# stmdc.net
KiCad netlist of a schematic drawn in EAGLE
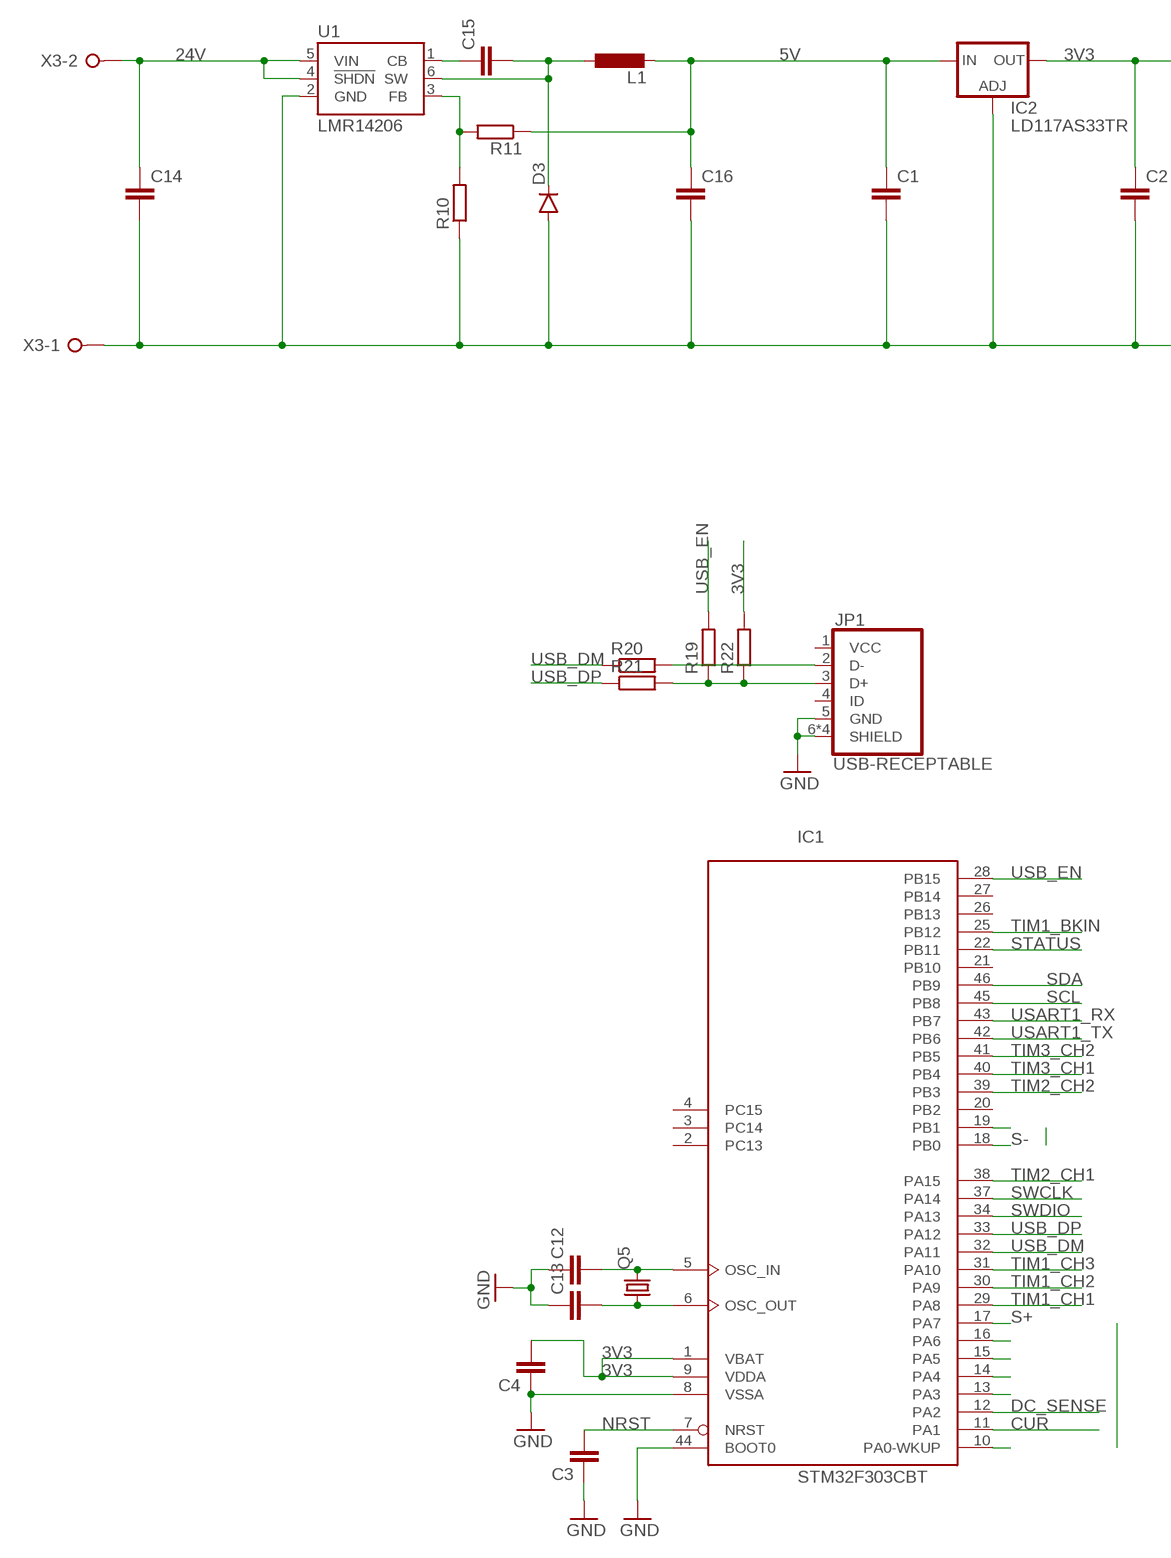
[diagram p0: schematic, sheet 1, part 1 of 2]
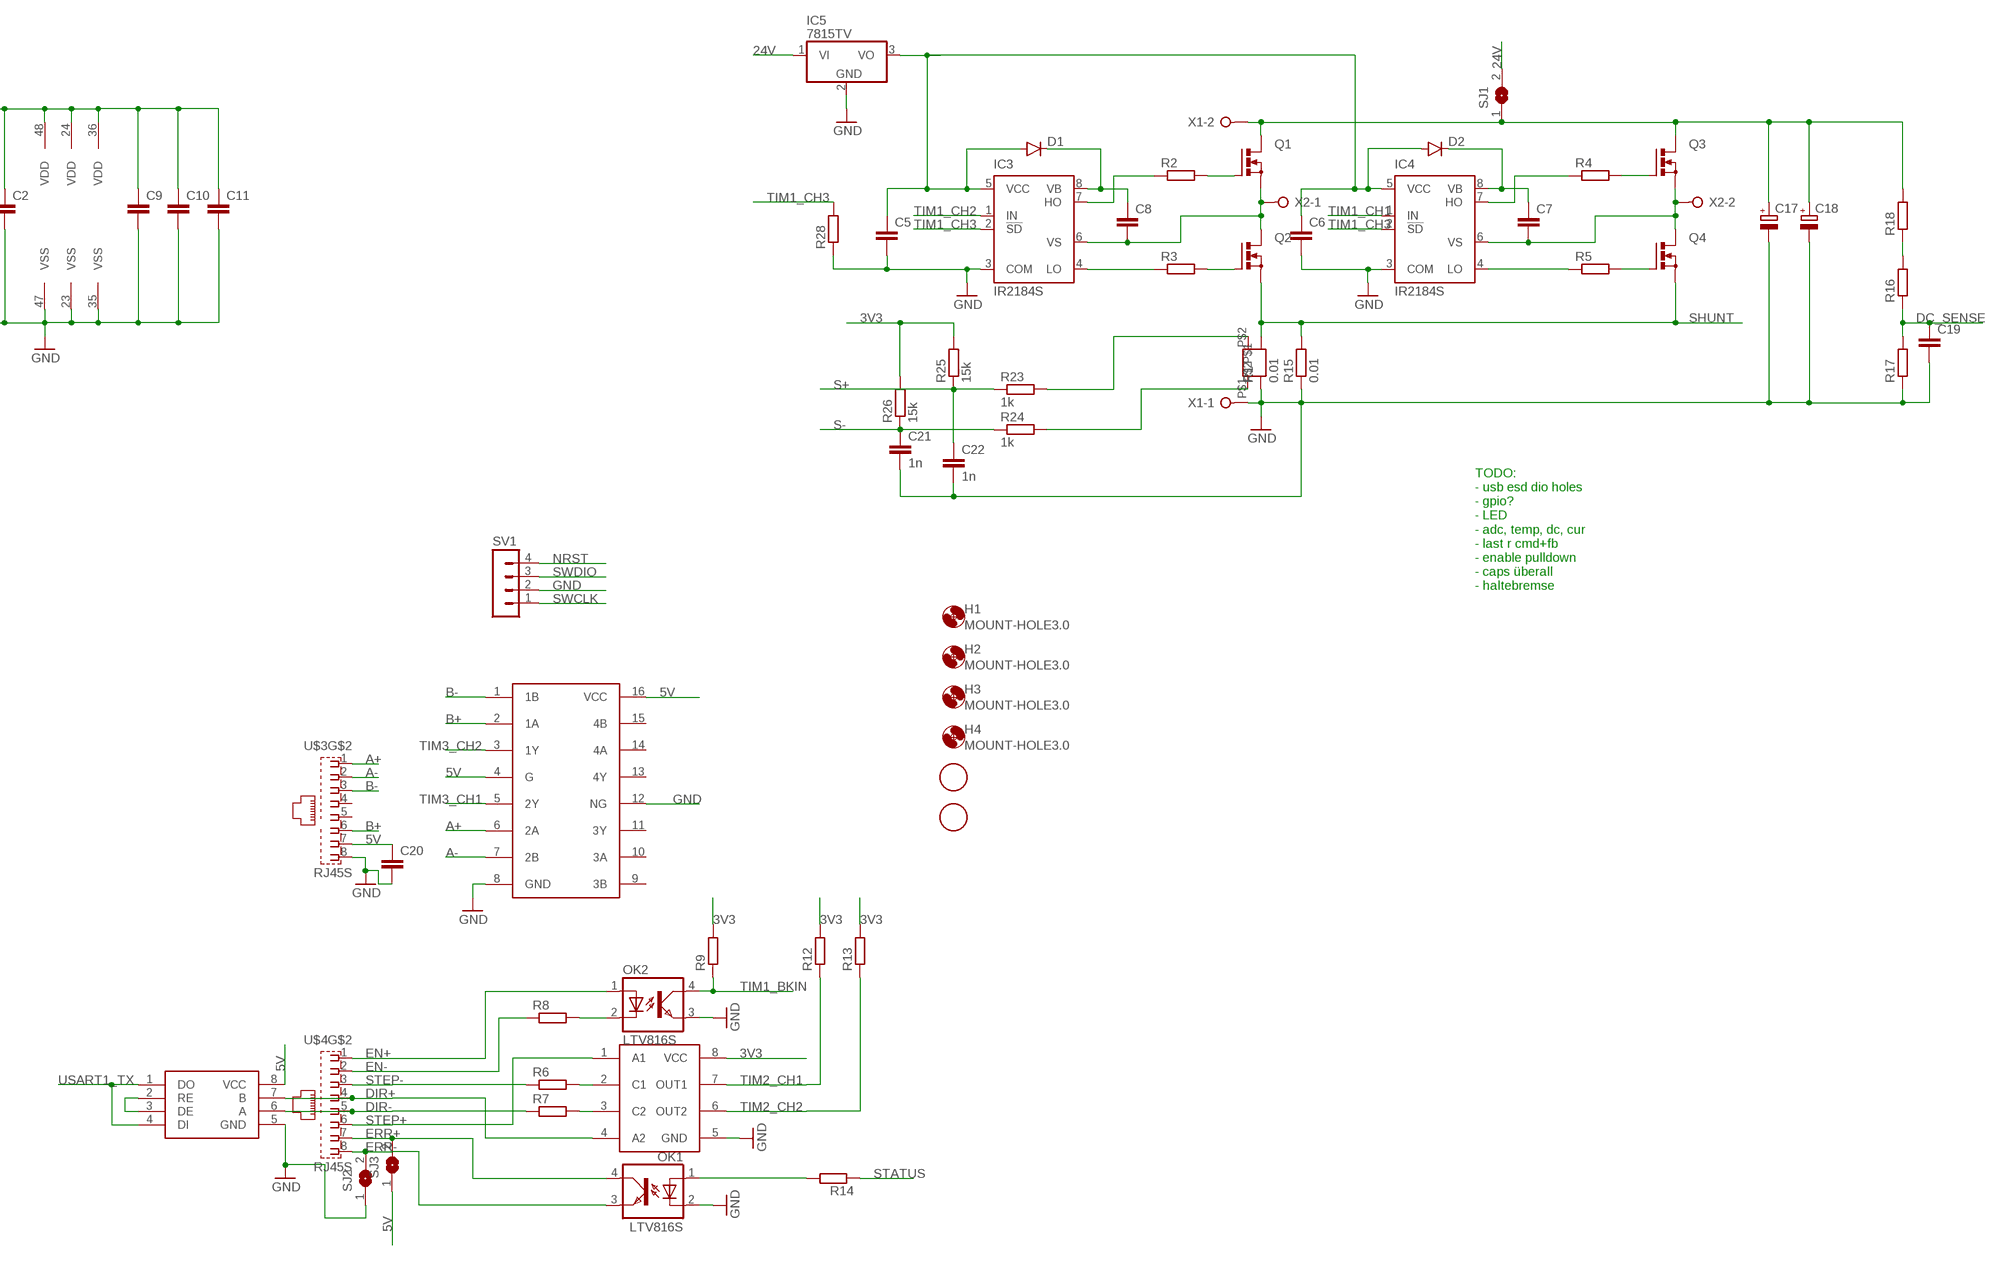
[diagram p1: schematic, sheet 1, part 2 of 2]

(export (version "E")
  (design (tool "Eeschema 10.0.6"))
  (components
    (comp (ref "C1")
      (value "C-EUC0805")
      (footprint "eagle-import:C0805")
      (libsource (lib "eagle-import") (part "C-EUC0805"))
    )
    (comp (ref "C2")
      (value "C-EUC0805")
      (footprint "eagle-import:C0805")
      (libsource (lib "eagle-import") (part "C-EUC0805"))
    )
    (comp (ref "C3")
      (value "C-EUC0603")
      (footprint "eagle-import:C0603")
      (libsource (lib "eagle-import") (part "C-EUC0603"))
    )
    (comp (ref "C4")
      (value "C-EUC0603")
      (footprint "eagle-import:C0603")
      (libsource (lib "eagle-import") (part "C-EUC0603"))
    )
    (comp (ref "C5")
      (value "C-EUC0603")
      (footprint "eagle-import:C0603")
      (libsource (lib "eagle-import") (part "C-EUC0603"))
    )
    (comp (ref "C6")
      (value "C-EUC0603")
      (footprint "eagle-import:C0603")
      (libsource (lib "eagle-import") (part "C-EUC0603"))
    )
    (comp (ref "C7")
      (value "C-EUC0805")
      (footprint "eagle-import:C0805")
      (libsource (lib "eagle-import") (part "C-EUC0805"))
    )
    (comp (ref "C8")
      (value "C-EUC0805")
      (footprint "eagle-import:C0805")
      (libsource (lib "eagle-import") (part "C-EUC0805"))
    )
    (comp (ref "C9")
      (value "C-EUC0603")
      (footprint "eagle-import:C0603")
      (libsource (lib "eagle-import") (part "C-EUC0603"))
    )
    (comp (ref "C10")
      (value "C-EUC0603")
      (footprint "eagle-import:C0603")
      (libsource (lib "eagle-import") (part "C-EUC0603"))
    )
    (comp (ref "C11")
      (value "C-EUC0603")
      (footprint "eagle-import:C0603")
      (libsource (lib "eagle-import") (part "C-EUC0603"))
    )
    (comp (ref "C12")
      (value "C-EUC0603")
      (footprint "eagle-import:C0603")
      (libsource (lib "eagle-import") (part "C-EUC0603"))
    )
    (comp (ref "C13")
      (value "C-EUC0603")
      (footprint "eagle-import:C0603")
      (libsource (lib "eagle-import") (part "C-EUC0603"))
    )
    (comp (ref "C14")
      (value "C-EUC1210")
      (footprint "eagle-import:C1210")
      (libsource (lib "eagle-import") (part "C-EUC1210"))
    )
    (comp (ref "C15")
      (value "C-EUC0805")
      (footprint "eagle-import:C0805")
      (libsource (lib "eagle-import") (part "C-EUC0805"))
    )
    (comp (ref "C16")
      (value "C-EUC1210")
      (footprint "eagle-import:C1210")
      (libsource (lib "eagle-import") (part "C-EUC1210"))
    )
    (comp (ref "C17")
      (value "CPOL-EUTT5D11L")
      (footprint "eagle-import:TT5D11L")
      (libsource (lib "eagle-import") (part "CPOL-EUTT5D11L"))
    )
    (comp (ref "C18")
      (value "CPOL-EUTT5D11L")
      (footprint "eagle-import:TT5D11L")
      (libsource (lib "eagle-import") (part "CPOL-EUTT5D11L"))
    )
    (comp (ref "C19")
      (value "C-EUC0603")
      (footprint "eagle-import:C0603")
      (libsource (lib "eagle-import") (part "C-EUC0603"))
    )
    (comp (ref "C20")
      (value "C-EUC0603")
      (footprint "eagle-import:C0603")
      (libsource (lib "eagle-import") (part "C-EUC0603"))
    )
    (comp (ref "C21")
      (value "1n")
      (footprint "eagle-import:C0603")
      (libsource (lib "eagle-import") (part "C-EUC0603"))
    )
    (comp (ref "C22")
      (value "1n")
      (footprint "eagle-import:C0603")
      (libsource (lib "eagle-import") (part "C-EUC0603"))
    )
    (comp (ref "D1")
      (value "DIODESMA")
      (footprint "eagle-import:SMA-DIODE")
      (libsource (lib "eagle-import") (part "DIODESMA"))
    )
    (comp (ref "D2")
      (value "DIODESMA")
      (footprint "eagle-import:SMA-DIODE")
      (libsource (lib "eagle-import") (part "DIODESMA"))
    )
    (comp (ref "D3")
      (value "DIODESMA")
      (footprint "eagle-import:SMA-DIODE")
      (libsource (lib "eagle-import") (part "DIODESMA"))
    )
    (comp (ref "H1")
      (value "MOUNT-HOLE3.0")
      (footprint "eagle-import:3,0")
      (libsource (lib "eagle-import") (part "MOUNT-HOLE3.0"))
    )
    (comp (ref "H2")
      (value "MOUNT-HOLE3.0")
      (footprint "eagle-import:3,0")
      (libsource (lib "eagle-import") (part "MOUNT-HOLE3.0"))
    )
    (comp (ref "H3")
      (value "MOUNT-HOLE3.0")
      (footprint "eagle-import:3,0")
      (libsource (lib "eagle-import") (part "MOUNT-HOLE3.0"))
    )
    (comp (ref "H4")
      (value "MOUNT-HOLE3.0")
      (footprint "eagle-import:3,0")
      (libsource (lib "eagle-import") (part "MOUNT-HOLE3.0"))
    )
    (comp (ref "IC1")
      (value "STM32F303CBT")
      (footprint "eagle-import:LQFP48")
      (libsource (lib "eagle-import") (part "STM32F303CTB"))
    )
    (comp (ref "IC2")
      (value "LD117AS33TR")
      (footprint "eagle-import:SOT223")
      (libsource (lib "eagle-import") (part "LD117A?S33TR"))
    )
    (comp (ref "IC3")
      (value "IR2184S")
      (footprint "eagle-import:SO08")
      (fields (field (name "MF") "INTERNATIONAL RECTIFIER(IR)") (field (name "MPN") "IR2184"))
      (libsource (lib "eagle-import") (part "IR2184S"))
    )
    (comp (ref "IC4")
      (value "IR2184S")
      (footprint "eagle-import:SO08")
      (fields (field (name "MF") "INTERNATIONAL RECTIFIER(IR)") (field (name "MPN") "IR2184"))
      (libsource (lib "eagle-import") (part "IR2184S"))
    )
    (comp (ref "IC5")
      (value "7815TV")
      (footprint "eagle-import:TO220V")
      (libsource (lib "eagle-import") (part "78TV15"))
    )
    (comp (ref "JP1")
      (value "USB-RECEPTABLE")
      (footprint "eagle-import:FCI-10103594-0001LF")
      (libsource (lib "eagle-import") (part "USB-RECEPTABLE"))
    )
    (comp (ref "L1")
      (value "L-EUPIS2816")
      (footprint "eagle-import:PIS2816")
      (libsource (lib "eagle-import") (part "L-EUPIS2816"))
    )
    (comp (ref "OK1")
      (value "LTV816S")
      (footprint "eagle-import:SMD4")
      (libsource (lib "eagle-import") (part "LTV816S"))
    )
    (comp (ref "OK2")
      (value "LTV816S")
      (footprint "eagle-import:SMD4")
      (libsource (lib "eagle-import") (part "LTV816S"))
    )
    (comp (ref "Q1")
      (value "PMOSFET_NTO220BH")
      (footprint "eagle-import:TO220BH")
      (libsource (lib "eagle-import") (part "PMOSFET_NTO220BH"))
    )
    (comp (ref "Q2")
      (value "PMOSFET_NTO220BH")
      (footprint "eagle-import:TO220BH")
      (libsource (lib "eagle-import") (part "PMOSFET_NTO220BH"))
    )
    (comp (ref "Q3")
      (value "PMOSFET_NTO220BH")
      (footprint "eagle-import:TO220BH")
      (libsource (lib "eagle-import") (part "PMOSFET_NTO220BH"))
    )
    (comp (ref "Q4")
      (value "PMOSFET_NTO220BH")
      (footprint "eagle-import:TO220BH")
      (libsource (lib "eagle-import") (part "PMOSFET_NTO220BH"))
    )
    (comp (ref "Q5")
      (value "CRYSTALCTS406")
      (footprint "eagle-import:CTS406")
      (libsource (lib "eagle-import") (part "CRYSTALCTS406"))
    )
    (comp (ref "R1")
      (value "0.01")
      (footprint "eagle-import:R2512")
      (libsource (lib "eagle-import") (part "R-SHUNT"))
    )
    (comp (ref "R2")
      (value "R-EU_R0603")
      (footprint "eagle-import:R0603")
      (libsource (lib "eagle-import") (part "R-EU_R0603"))
    )
    (comp (ref "R3")
      (value "R-EU_R0603")
      (footprint "eagle-import:R0603")
      (libsource (lib "eagle-import") (part "R-EU_R0603"))
    )
    (comp (ref "R4")
      (value "R-EU_R0603")
      (footprint "eagle-import:R0603")
      (libsource (lib "eagle-import") (part "R-EU_R0603"))
    )
    (comp (ref "R5")
      (value "R-EU_R0603")
      (footprint "eagle-import:R0603")
      (libsource (lib "eagle-import") (part "R-EU_R0603"))
    )
    (comp (ref "R6")
      (value "R-EU_R0603")
      (footprint "eagle-import:R0603")
      (libsource (lib "eagle-import") (part "R-EU_R0603"))
    )
    (comp (ref "R7")
      (value "R-EU_R0603")
      (footprint "eagle-import:R0603")
      (libsource (lib "eagle-import") (part "R-EU_R0603"))
    )
    (comp (ref "R8")
      (value "R-EU_R0603")
      (footprint "eagle-import:R0603")
      (libsource (lib "eagle-import") (part "R-EU_R0603"))
    )
    (comp (ref "R9")
      (value "R-EU_R0603")
      (footprint "eagle-import:R0603")
      (libsource (lib "eagle-import") (part "R-EU_R0603"))
    )
    (comp (ref "R10")
      (value "R-EU_R0603")
      (footprint "eagle-import:R0603")
      (libsource (lib "eagle-import") (part "R-EU_R0603"))
    )
    (comp (ref "R11")
      (value "R-EU_R0603")
      (footprint "eagle-import:R0603")
      (libsource (lib "eagle-import") (part "R-EU_R0603"))
    )
    (comp (ref "R12")
      (value "R-EU_R0603")
      (footprint "eagle-import:R0603")
      (libsource (lib "eagle-import") (part "R-EU_R0603"))
    )
    (comp (ref "R13")
      (value "R-EU_R0603")
      (footprint "eagle-import:R0603")
      (libsource (lib "eagle-import") (part "R-EU_R0603"))
    )
    (comp (ref "R14")
      (value "R-EU_R0603")
      (footprint "eagle-import:R0603")
      (libsource (lib "eagle-import") (part "R-EU_R0603"))
    )
    (comp (ref "R15")
      (value "0.01")
      (footprint "eagle-import:R2512")
      (libsource (lib "eagle-import") (part "R-EU_R2512"))
    )
    (comp (ref "R16")
      (value "R-EU_R0805")
      (footprint "eagle-import:R0805")
      (libsource (lib "eagle-import") (part "R-EU_R0805"))
    )
    (comp (ref "R17")
      (value "R-EU_R0603")
      (footprint "eagle-import:R0603")
      (libsource (lib "eagle-import") (part "R-EU_R0603"))
    )
    (comp (ref "R18")
      (value "R-EU_R0805")
      (footprint "eagle-import:R0805")
      (libsource (lib "eagle-import") (part "R-EU_R0805"))
    )
    (comp (ref "R19")
      (value "R-EU_R0603")
      (footprint "eagle-import:R0603")
      (libsource (lib "eagle-import") (part "R-EU_R0603"))
    )
    (comp (ref "R20")
      (value "R-EU_R0603")
      (footprint "eagle-import:R0603")
      (libsource (lib "eagle-import") (part "R-EU_R0603"))
    )
    (comp (ref "R21")
      (value "R-EU_R0603")
      (footprint "eagle-import:R0603")
      (libsource (lib "eagle-import") (part "R-EU_R0603"))
    )
    (comp (ref "R22")
      (value "R-EU_R0603")
      (footprint "eagle-import:R0603")
      (libsource (lib "eagle-import") (part "R-EU_R0603"))
    )
    (comp (ref "R23")
      (value "1k")
      (footprint "eagle-import:R0603")
      (libsource (lib "eagle-import") (part "R-EU_R0603"))
    )
    (comp (ref "R24")
      (value "1k")
      (footprint "eagle-import:R0603")
      (libsource (lib "eagle-import") (part "R-EU_R0603"))
    )
    (comp (ref "R25")
      (value "15k")
      (footprint "eagle-import:R0603")
      (libsource (lib "eagle-import") (part "R-EU_R0603"))
    )
    (comp (ref "R26")
      (value "15k")
      (footprint "eagle-import:R0603")
      (libsource (lib "eagle-import") (part "R-EU_R0603"))
    )
    (comp (ref "R28")
      (value "R-EU_R0603")
      (footprint "eagle-import:R0603")
      (libsource (lib "eagle-import") (part "R-EU_R0603"))
    )
    (comp (ref "SJ1") (value "SJ") (footprint "eagle-import:SJ") (libsource (lib "eagle-import") (part "SJ")))
    (comp (ref "SJ2") (value "SJ") (footprint "eagle-import:SJ") (libsource (lib "eagle-import") (part "SJ")))
    (comp (ref "SJ3") (value "SJ") (footprint "eagle-import:SJ") (libsource (lib "eagle-import") (part "SJ")))
    (comp (ref "SV1")
      (value "MA04-1")
      (footprint "eagle-import:MA04-1")
      (libsource (lib "eagle-import") (part "MA04-1"))
    )
    (comp (ref "U$1")
      (value "AM26LS32ACD")
      (footprint "eagle-import:SO16")
      (libsource (lib "eagle-import") (part "AM26LS32ACD"))
    )
    (comp (ref "U$2")
      (value "HCPL-053L-SMD")
      (footprint "eagle-import:SO08")
      (libsource (lib "eagle-import") (part "HCPL-053L-SMD"))
    )
    (comp (ref "U$3")
      (value "RJ45S")
      (footprint "eagle-import:RJ45")
      (libsource (lib "eagle-import") (part "RJ45S"))
    )
    (comp (ref "U$4")
      (value "RJ45S")
      (footprint "eagle-import:RJ45")
      (libsource (lib "eagle-import") (part "RJ45S"))
    )
    (comp (ref "U$5")
      (value "FIDUCIAL")
      (footprint "eagle-import:FIDUCIAL_1MM")
      (libsource (lib "eagle-import") (part "FIDUCIAL"))
    )
    (comp (ref "U$6")
      (value "FIDUCIAL")
      (footprint "eagle-import:FIDUCIAL_1MM")
      (libsource (lib "eagle-import") (part "FIDUCIAL"))
    )
    (comp (ref "U$7")
      (value "ADM485SOIC8")
      (footprint "eagle-import:SOIC08")
      (libsource (lib "eagle-import") (part "ADM485SOIC8"))
    )
    (comp (ref "U1")
      (value "LMR14206")
      (footprint "eagle-import:SOT23-6")
      (libsource (lib "eagle-import") (part "LMR14206SOT-23"))
    )
    (comp (ref "X1")
      (value "AKL230-02")
      (footprint "eagle-import:AKL230-02")
      (libsource (lib "eagle-import") (part "AKL230-02"))
    )
    (comp (ref "X2")
      (value "AKL230-02")
      (footprint "eagle-import:AKL230-02")
      (libsource (lib "eagle-import") (part "AKL230-02"))
    )
    (comp (ref "X3")
      (value "AKL230-02")
      (footprint "eagle-import:AKL230-02")
      (libsource (lib "eagle-import") (part "AKL230-02"))
    )
  )
  (nets
    (net (code "1") (name "/3V3") (class "Default")
      (node (ref "C10") (pin "1") (pinfunction "1_1") (pintype "passive"))
      (node (ref "C11") (pin "1") (pinfunction "1_1") (pintype "passive"))
      (node (ref "C2") (pin "1") (pinfunction "1_1") (pintype "passive"))
      (node (ref "C4") (pin "2") (pinfunction "2_2") (pintype "passive"))
      (node (ref "C9") (pin "1") (pinfunction "1_1") (pintype "passive"))
      (node (ref "IC1") (pin "1") (pinfunction "VBAT_1") (pintype "power_in"))
      (node (ref "IC1") (pin "24") (pinfunction "VDD_24") (pintype "power_in"))
      (node (ref "IC1") (pin "36") (pinfunction "VDD_36") (pintype "power_in"))
      (node (ref "IC1") (pin "48") (pinfunction "VDD_48") (pintype "power_in"))
      (node (ref "IC1") (pin "9") (pinfunction "VDDA_9") (pintype "power_in"))
      (node (ref "IC2") (pin "4") (pinfunction "OUT_4") (pintype "passive"))
      (node (ref "R12") (pin "2") (pinfunction "2_2") (pintype "passive"))
      (node (ref "R13") (pin "2") (pinfunction "2_2") (pintype "passive"))
      (node (ref "R22") (pin "2") (pinfunction "2_2") (pintype "passive"))
      (node (ref "R25") (pin "2") (pinfunction "2_2") (pintype "passive"))
      (node (ref "R26") (pin "2") (pinfunction "2_2") (pintype "passive"))
      (node (ref "R9") (pin "2") (pinfunction "2_2") (pintype "passive"))
      (node (ref "U$2") (pin "8") (pinfunction "VCC_8") (pintype "bidirectional"))
    )
    (net (code "2") (name "/5V") (class "Default")
      (node (ref "C1") (pin "1") (pinfunction "1_1") (pintype "passive"))
      (node (ref "C16") (pin "1") (pinfunction "1_1") (pintype "passive"))
      (node (ref "C20") (pin "1") (pinfunction "1_1") (pintype "passive"))
      (node (ref "IC2") (pin "3") (pinfunction "IN_3") (pintype "input"))
      (node (ref "L1") (pin "2") (pinfunction "2_2") (pintype "passive"))
      (node (ref "R11") (pin "1") (pinfunction "1_1") (pintype "passive"))
      (node (ref "SJ3") (pin "1") (pinfunction "1_1") (pintype "passive"))
      (node (ref "U$1") (pin "16") (pinfunction "VCC_16") (pintype "bidirectional"))
      (node (ref "U$1") (pin "4") (pinfunction "G_4") (pintype "bidirectional"))
      (node (ref "U$3") (pin "7") (pinfunction "7_7") (pintype "passive"))
      (node (ref "U$7") (pin "8") (pinfunction "VCC_8") (pintype "bidirectional"))
    )
    (net (code "3") (name "/24V") (class "Default")
      (node (ref "C14") (pin "1") (pinfunction "1_1") (pintype "passive"))
      (node (ref "IC5") (pin "1") (pinfunction "VI_1") (pintype "input"))
      (node (ref "SJ1") (pin "2") (pinfunction "2_2") (pintype "passive"))
      (node (ref "U1") (pin "4") (pinfunction "~{SHDN}_4") (pintype "bidirectional"))
      (node (ref "U1") (pin "5") (pinfunction "VIN_5") (pintype "bidirectional"))
      (node (ref "X3") (pin "2") (pinfunction "KL_2") (pintype "passive"))
    )
    (net (code "4") (name "/A+") (class "Default")
      (node (ref "U$1") (pin "6") (pinfunction "2A_6") (pintype "bidirectional"))
      (node (ref "U$3") (pin "1") (pinfunction "1_1") (pintype "passive"))
    )
    (net (code "5") (name "/A-") (class "Default")
      (node (ref "U$1") (pin "7") (pinfunction "2B_7") (pintype "bidirectional"))
      (node (ref "U$3") (pin "2") (pinfunction "2_2") (pintype "passive"))
    )
    (net (code "6") (name "/B+") (class "Default")
      (node (ref "U$1") (pin "2") (pinfunction "1A_2") (pintype "bidirectional"))
      (node (ref "U$3") (pin "6") (pinfunction "6_6") (pintype "passive"))
    )
    (net (code "7") (name "/B-") (class "Default")
      (node (ref "U$1") (pin "1") (pinfunction "1B_1") (pintype "bidirectional"))
      (node (ref "U$3") (pin "3") (pinfunction "3_3") (pintype "passive"))
    )
    (net (code "8") (name "/CUR") (class "Default")
      (node (ref "IC1") (pin "11") (pinfunction "PA1_11") (pintype "bidirectional"))
    )
    (net (code "9") (name "/DC_SENSE") (class "Default")
      (node (ref "C19") (pin "1") (pinfunction "1_1") (pintype "passive"))
      (node (ref "IC1") (pin "12") (pinfunction "PA2_12") (pintype "bidirectional"))
      (node (ref "R16") (pin "1") (pinfunction "1_1") (pintype "passive"))
      (node (ref "R17") (pin "2") (pinfunction "2_2") (pintype "passive"))
    )
    (net (code "10") (name "/DIR+") (class "Default")
      (node (ref "U$2") (pin "4") (pinfunction "A2_4") (pintype "bidirectional"))
      (node (ref "U$4") (pin "4") (pinfunction "4_4") (pintype "passive"))
      (node (ref "U$7") (pin "7") (pinfunction "B_7") (pintype "bidirectional"))
    )
    (net (code "11") (name "/DIR-") (class "Default")
      (node (ref "R7") (pin "1") (pinfunction "1_1") (pintype "passive"))
      (node (ref "U$4") (pin "5") (pinfunction "5_5") (pintype "passive"))
      (node (ref "U$7") (pin "6") (pinfunction "A_6") (pintype "bidirectional"))
    )
    (net (code "12") (name "/EN+") (class "Default")
      (node (ref "OK2") (pin "1") (pinfunction "A_1") (pintype "passive"))
      (node (ref "U$4") (pin "1") (pinfunction "1_1") (pintype "passive"))
    )
    (net (code "13") (name "/EN-") (class "Default")
      (node (ref "R8") (pin "1") (pinfunction "1_1") (pintype "passive"))
      (node (ref "U$4") (pin "2") (pinfunction "2_2") (pintype "passive"))
    )
    (net (code "14") (name "/ERR+") (class "Default")
      (node (ref "OK1") (pin "4") (pinfunction "COL_4") (pintype "passive"))
      (node (ref "SJ3") (pin "2") (pinfunction "2_2") (pintype "passive"))
      (node (ref "U$4") (pin "7") (pinfunction "7_7") (pintype "passive"))
    )
    (net (code "15") (name "/ERR-") (class "Default")
      (node (ref "OK1") (pin "3") (pinfunction "EMIT_3") (pintype "passive"))
      (node (ref "SJ2") (pin "2") (pinfunction "2_2") (pintype "passive"))
      (node (ref "U$4") (pin "8") (pinfunction "8_8") (pintype "passive"))
    )
    (net (code "16") (name "/NRST") (class "Default")
      (node (ref "C3") (pin "2") (pinfunction "2_2") (pintype "passive"))
      (node (ref "IC1") (pin "7") (pinfunction "NRST_7") (pintype "bidirectional"))
      (node (ref "SV1") (pin "4") (pinfunction "4_4") (pintype "passive"))
    )
    (net (code "17") (name "/S+") (class "Default")
      (node (ref "C22") (pin "1") (pinfunction "1_1") (pintype "passive"))
      (node (ref "IC1") (pin "17") (pinfunction "PA7_17") (pintype "bidirectional"))
      (node (ref "R23") (pin "1") (pinfunction "1_1") (pintype "passive"))
      (node (ref "R25") (pin "1") (pinfunction "1_1") (pintype "passive"))
    )
    (net (code "18") (name "/S-") (class "Default")
      (node (ref "C21") (pin "1") (pinfunction "1_1") (pintype "passive"))
      (node (ref "IC1") (pin "18") (pinfunction "PB0_18") (pintype "bidirectional"))
      (node (ref "R24") (pin "1") (pinfunction "1_1") (pintype "passive"))
      (node (ref "R26") (pin "1") (pinfunction "1_1") (pintype "passive"))
    )
    (net (code "19") (name "/SCL") (class "Default")
      (node (ref "IC1") (pin "45") (pinfunction "PB8_45") (pintype "bidirectional"))
    )
    (net (code "20") (name "/SDA") (class "Default")
      (node (ref "IC1") (pin "46") (pinfunction "PB9_46") (pintype "bidirectional"))
    )
    (net (code "21") (name "/SHUNT") (class "Default")
      (node (ref "Q2") (pin "S") (pinfunction "S_S") (pintype "passive"))
      (node (ref "Q4") (pin "S") (pinfunction "S_S") (pintype "passive"))
      (node (ref "R1") (pin "2") (pinfunction "2_2") (pintype "passive"))
      (node (ref "R15") (pin "2") (pinfunction "2_2") (pintype "passive"))
    )
    (net (code "22") (name "/STATUS") (class "Default")
      (node (ref "IC1") (pin "22") (pinfunction "PB11_22") (pintype "bidirectional"))
      (node (ref "R14") (pin "1") (pinfunction "1_1") (pintype "passive"))
    )
    (net (code "23") (name "/STEP+") (class "Default")
      (node (ref "U$2") (pin "1") (pinfunction "A1_1") (pintype "bidirectional"))
      (node (ref "U$4") (pin "6") (pinfunction "6_6") (pintype "passive"))
    )
    (net (code "24") (name "/STEP-") (class "Default")
      (node (ref "R6") (pin "1") (pinfunction "1_1") (pintype "passive"))
      (node (ref "U$4") (pin "3") (pinfunction "3_3") (pintype "passive"))
    )
    (net (code "25") (name "/SWCLK") (class "Default")
      (node (ref "IC1") (pin "37") (pinfunction "PA14_37") (pintype "bidirectional"))
      (node (ref "SV1") (pin "1") (pinfunction "1_1") (pintype "passive"))
    )
    (net (code "26") (name "/SWDIO") (class "Default")
      (node (ref "IC1") (pin "34") (pinfunction "PA13_34") (pintype "bidirectional"))
      (node (ref "SV1") (pin "3") (pinfunction "3_3") (pintype "passive"))
    )
    (net (code "27") (name "/TIM1_BKIN") (class "Default")
      (node (ref "IC1") (pin "25") (pinfunction "PB12_25") (pintype "bidirectional"))
      (node (ref "OK2") (pin "4") (pinfunction "COL_4") (pintype "passive"))
      (node (ref "R9") (pin "1") (pinfunction "1_1") (pintype "passive"))
    )
    (net (code "28") (name "/TIM1_CH1") (class "Default")
      (node (ref "IC1") (pin "29") (pinfunction "PA8_29") (pintype "bidirectional"))
      (node (ref "IC4") (pin "1") (pinfunction "IN_1") (pintype "input"))
    )
    (net (code "29") (name "/TIM1_CH2") (class "Default")
      (node (ref "IC1") (pin "30") (pinfunction "PA9_30") (pintype "bidirectional"))
      (node (ref "IC3") (pin "1") (pinfunction "IN_1") (pintype "input"))
    )
    (net (code "30") (name "/TIM1_CH3") (class "Default")
      (node (ref "IC1") (pin "31") (pinfunction "PA10_31") (pintype "bidirectional"))
      (node (ref "IC3") (pin "2") (pinfunction "~{SD}_2") (pintype "input"))
      (node (ref "IC4") (pin "2") (pinfunction "~{SD}_2") (pintype "input"))
      (node (ref "R28") (pin "2") (pinfunction "2_2") (pintype "passive"))
    )
    (net (code "31") (name "/TIM2_CH1") (class "Default")
      (node (ref "IC1") (pin "38") (pinfunction "PA15_38") (pintype "bidirectional"))
      (node (ref "R12") (pin "1") (pinfunction "1_1") (pintype "passive"))
      (node (ref "U$2") (pin "7") (pinfunction "OUT1_7") (pintype "bidirectional"))
    )
    (net (code "32") (name "/TIM2_CH2") (class "Default")
      (node (ref "IC1") (pin "39") (pinfunction "PB3_39") (pintype "bidirectional"))
      (node (ref "R13") (pin "1") (pinfunction "1_1") (pintype "passive"))
      (node (ref "U$2") (pin "6") (pinfunction "OUT2_6") (pintype "bidirectional"))
    )
    (net (code "33") (name "/TIM3_CH1") (class "Default")
      (node (ref "IC1") (pin "40") (pinfunction "PB4_40") (pintype "bidirectional"))
      (node (ref "U$1") (pin "5") (pinfunction "2Y_5") (pintype "bidirectional"))
    )
    (net (code "34") (name "/TIM3_CH2") (class "Default")
      (node (ref "IC1") (pin "41") (pinfunction "PB5_41") (pintype "bidirectional"))
      (node (ref "U$1") (pin "3") (pinfunction "1Y_3") (pintype "bidirectional"))
    )
    (net (code "35") (name "/USART1_RX") (class "Default")
      (node (ref "IC1") (pin "43") (pinfunction "PB7_43") (pintype "bidirectional"))
    )
    (net (code "36") (name "/USART1_TX") (class "Default")
      (node (ref "IC1") (pin "42") (pinfunction "PB6_42") (pintype "bidirectional"))
      (node (ref "U$7") (pin "1") (pinfunction "DO_1") (pintype "bidirectional"))
      (node (ref "U$7") (pin "4") (pinfunction "DI_4") (pintype "bidirectional"))
    )
    (net (code "37") (name "/USB_DM") (class "Default")
      (node (ref "IC1") (pin "32") (pinfunction "PA11_32") (pintype "bidirectional"))
      (node (ref "R20") (pin "1") (pinfunction "1_1") (pintype "passive"))
    )
    (net (code "38") (name "/USB_DP") (class "Default")
      (node (ref "IC1") (pin "33") (pinfunction "PA12_33") (pintype "bidirectional"))
      (node (ref "R21") (pin "1") (pinfunction "1_1") (pintype "passive"))
    )
    (net (code "39") (name "/USB_EN") (class "Default")
      (node (ref "IC1") (pin "28") (pinfunction "PB15_28") (pintype "bidirectional"))
      (node (ref "R19") (pin "2") (pinfunction "2_2") (pintype "passive"))
    )
    (net (code "40") (name "GND") (class "Default")
      (node (ref "C1") (pin "2") (pinfunction "2_2") (pintype "passive"))
      (node (ref "C10") (pin "2") (pinfunction "2_2") (pintype "passive"))
      (node (ref "C11") (pin "2") (pinfunction "2_2") (pintype "passive"))
      (node (ref "C12") (pin "1") (pinfunction "1_1") (pintype "passive"))
      (node (ref "C13") (pin "1") (pinfunction "1_1") (pintype "passive"))
      (node (ref "C14") (pin "2") (pinfunction "2_2") (pintype "passive"))
      (node (ref "C16") (pin "2") (pinfunction "2_2") (pintype "passive"))
      (node (ref "C17") (pin "-") (pinfunction "-_-") (pintype "passive"))
      (node (ref "C18") (pin "-") (pinfunction "-_-") (pintype "passive"))
      (node (ref "C19") (pin "2") (pinfunction "2_2") (pintype "passive"))
      (node (ref "C2") (pin "2") (pinfunction "2_2") (pintype "passive"))
      (node (ref "C20") (pin "2") (pinfunction "2_2") (pintype "passive"))
      (node (ref "C21") (pin "2") (pinfunction "2_2") (pintype "passive"))
      (node (ref "C22") (pin "2") (pinfunction "2_2") (pintype "passive"))
      (node (ref "C3") (pin "1") (pinfunction "1_1") (pintype "passive"))
      (node (ref "C4") (pin "1") (pinfunction "1_1") (pintype "passive"))
      (node (ref "C5") (pin "2") (pinfunction "2_2") (pintype "passive"))
      (node (ref "C6") (pin "2") (pinfunction "2_2") (pintype "passive"))
      (node (ref "C9") (pin "2") (pinfunction "2_2") (pintype "passive"))
      (node (ref "D3") (pin "A") (pinfunction "A_A") (pintype "passive"))
      (node (ref "IC1") (pin "23") (pinfunction "VSS_23") (pintype "power_in"))
      (node (ref "IC1") (pin "35") (pinfunction "VSS_35") (pintype "power_in"))
      (node (ref "IC1") (pin "44") (pinfunction "BOOT0_44") (pintype "input"))
      (node (ref "IC1") (pin "47") (pinfunction "VSS_47") (pintype "power_in"))
      (node (ref "IC1") (pin "8") (pinfunction "VSSA_8") (pintype "power_in"))
      (node (ref "IC2") (pin "1") (pinfunction "ADJ_1") (pintype "input"))
      (node (ref "IC3") (pin "3") (pinfunction "COM_3") (pintype "power_in"))
      (node (ref "IC4") (pin "3") (pinfunction "COM_3") (pintype "power_in"))
      (node (ref "IC5") (pin "2") (pinfunction "GND_2") (pintype "passive"))
      (node (ref "JP1") (pin "5") (pinfunction "GND_5") (pintype "bidirectional"))
      (node (ref "JP1") (pin "6") (pinfunction "SHIELD_6") (pintype "bidirectional"))
      (node (ref "JP1") (pin "7") (pinfunction "SHIELD_7") (pintype "bidirectional"))
      (node (ref "JP1") (pin "8") (pinfunction "SHIELD_8") (pintype "bidirectional"))
      (node (ref "JP1") (pin "9") (pinfunction "SHIELD_9") (pintype "bidirectional"))
      (node (ref "OK1") (pin "2") (pinfunction "C_2") (pintype "passive"))
      (node (ref "OK2") (pin "3") (pinfunction "EMIT_3") (pintype "passive"))
      (node (ref "R1") (pin "1") (pinfunction "1_1") (pintype "passive"))
      (node (ref "R10") (pin "1") (pinfunction "1_1") (pintype "passive"))
      (node (ref "R15") (pin "1") (pinfunction "1_1") (pintype "passive"))
      (node (ref "R17") (pin "1") (pinfunction "1_1") (pintype "passive"))
      (node (ref "R28") (pin "1") (pinfunction "1_1") (pintype "passive"))
      (node (ref "SJ2") (pin "1") (pinfunction "1_1") (pintype "passive"))
      (node (ref "SV1") (pin "2") (pinfunction "2_2") (pintype "passive"))
      (node (ref "U$1") (pin "12") (pinfunction "NG_12") (pintype "bidirectional"))
      (node (ref "U$1") (pin "8") (pinfunction "GND_8") (pintype "bidirectional"))
      (node (ref "U$2") (pin "5") (pinfunction "GND_5") (pintype "bidirectional"))
      (node (ref "U$3") (pin "8") (pinfunction "8_8") (pintype "passive"))
      (node (ref "U$7") (pin "5") (pinfunction "GND_5") (pintype "bidirectional"))
      (node (ref "U1") (pin "2") (pinfunction "GND_2") (pintype "bidirectional"))
      (node (ref "X1") (pin "1") (pinfunction "KL_1") (pintype "passive"))
      (node (ref "X3") (pin "1") (pinfunction "KL_1") (pintype "passive"))
    )
    (net (code "41") (name "Net-(IC1A-OSC_IN)") (class "Default")
      (node (ref "C12") (pin "2") (pinfunction "2_2") (pintype "passive"))
      (node (ref "IC1") (pin "5") (pinfunction "OSC_IN_5") (pintype "bidirectional"))
      (node (ref "Q5") (pin "3") (pinfunction "2_3") (pintype "passive"))
    )
    (net (code "42") (name "Net-(IC1A-OSC_OUT)") (class "Default")
      (node (ref "C13") (pin "2") (pinfunction "2_2") (pintype "passive"))
      (node (ref "IC1") (pin "6") (pinfunction "OSC_OUT_6") (pintype "bidirectional"))
      (node (ref "Q5") (pin "1") (pinfunction "1_1") (pintype "passive"))
    )
    (net (code "43") (name "Net-(IC3-HO)") (class "Default")
      (node (ref "IC3") (pin "7") (pinfunction "HO_7") (pintype "passive"))
      (node (ref "R2") (pin "1") (pinfunction "1_1") (pintype "passive"))
    )
    (net (code "44") (name "Net-(IC3-LO)") (class "Default")
      (node (ref "IC3") (pin "4") (pinfunction "LO_4") (pintype "output"))
      (node (ref "R3") (pin "1") (pinfunction "1_1") (pintype "passive"))
    )
    (net (code "45") (name "Net-(IC3-VB)") (class "Default")
      (node (ref "C8") (pin "1") (pinfunction "1_1") (pintype "passive"))
      (node (ref "D1") (pin "C") (pinfunction "C_C") (pintype "passive"))
      (node (ref "IC3") (pin "8") (pinfunction "VB_8") (pintype "output"))
    )
    (net (code "46") (name "Net-(IC3-VCC)") (class "Default")
      (node (ref "C5") (pin "1") (pinfunction "1_1") (pintype "passive"))
      (node (ref "C6") (pin "1") (pinfunction "1_1") (pintype "passive"))
      (node (ref "D1") (pin "A") (pinfunction "A_A") (pintype "passive"))
      (node (ref "D2") (pin "A") (pinfunction "A_A") (pintype "passive"))
      (node (ref "IC3") (pin "5") (pinfunction "VCC_5") (pintype "power_in"))
      (node (ref "IC4") (pin "5") (pinfunction "VCC_5") (pintype "power_in"))
      (node (ref "IC5") (pin "3") (pinfunction "VO_3") (pintype "passive"))
    )
    (net (code "47") (name "Net-(IC3-VS)") (class "Default")
      (node (ref "C8") (pin "2") (pinfunction "2_2") (pintype "passive"))
      (node (ref "IC3") (pin "6") (pinfunction "VS_6") (pintype "input"))
      (node (ref "Q1") (pin "S") (pinfunction "S_S") (pintype "passive"))
      (node (ref "Q2") (pin "D") (pinfunction "D_D") (pintype "passive"))
      (node (ref "X2") (pin "1") (pinfunction "KL_1") (pintype "passive"))
    )
    (net (code "48") (name "Net-(IC4-HO)") (class "Default")
      (node (ref "IC4") (pin "7") (pinfunction "HO_7") (pintype "passive"))
      (node (ref "R4") (pin "1") (pinfunction "1_1") (pintype "passive"))
    )
    (net (code "49") (name "Net-(IC4-LO)") (class "Default")
      (node (ref "IC4") (pin "4") (pinfunction "LO_4") (pintype "output"))
      (node (ref "R5") (pin "1") (pinfunction "1_1") (pintype "passive"))
    )
    (net (code "50") (name "Net-(IC4-VB)") (class "Default")
      (node (ref "C7") (pin "1") (pinfunction "1_1") (pintype "passive"))
      (node (ref "D2") (pin "C") (pinfunction "C_C") (pintype "passive"))
      (node (ref "IC4") (pin "8") (pinfunction "VB_8") (pintype "output"))
    )
    (net (code "51") (name "Net-(IC4-VS)") (class "Default")
      (node (ref "C7") (pin "2") (pinfunction "2_2") (pintype "passive"))
      (node (ref "IC4") (pin "6") (pinfunction "VS_6") (pintype "input"))
      (node (ref "Q3") (pin "S") (pinfunction "S_S") (pintype "passive"))
      (node (ref "Q4") (pin "D") (pinfunction "D_D") (pintype "passive"))
      (node (ref "X2") (pin "2") (pinfunction "KL_2") (pintype "passive"))
    )
    (net (code "52") (name "Net-(JP1-D+)") (class "Default")
      (node (ref "JP1") (pin "3") (pinfunction "D+_3") (pintype "bidirectional"))
      (node (ref "R19") (pin "1") (pinfunction "1_1") (pintype "passive"))
      (node (ref "R21") (pin "2") (pinfunction "2_2") (pintype "passive"))
      (node (ref "R22") (pin "1") (pinfunction "1_1") (pintype "passive"))
    )
    (net (code "53") (name "Net-(JP1-D-)") (class "Default")
      (node (ref "JP1") (pin "2") (pinfunction "D-_2") (pintype "bidirectional"))
      (node (ref "R20") (pin "2") (pinfunction "2_2") (pintype "passive"))
    )
    (net (code "54") (name "Net-(OK1-A)") (class "Default")
      (node (ref "OK1") (pin "1") (pinfunction "A_1") (pintype "passive"))
      (node (ref "R14") (pin "2") (pinfunction "2_2") (pintype "passive"))
    )
    (net (code "55") (name "Net-(OK2-C)") (class "Default")
      (node (ref "OK2") (pin "2") (pinfunction "C_2") (pintype "passive"))
      (node (ref "R8") (pin "2") (pinfunction "2_2") (pintype "passive"))
    )
    (net (code "56") (name "Net-(Q1-PadG)") (class "Default")
      (node (ref "Q1") (pin "G") (pinfunction "G_G") (pintype "passive"))
      (node (ref "R2") (pin "2") (pinfunction "2_2") (pintype "passive"))
    )
    (net (code "57") (name "Net-(Q2-PadG)") (class "Default")
      (node (ref "Q2") (pin "G") (pinfunction "G_G") (pintype "passive"))
      (node (ref "R3") (pin "2") (pinfunction "2_2") (pintype "passive"))
    )
    (net (code "58") (name "Net-(Q3-PadG)") (class "Default")
      (node (ref "Q3") (pin "G") (pinfunction "G_G") (pintype "passive"))
      (node (ref "R4") (pin "2") (pinfunction "2_2") (pintype "passive"))
    )
    (net (code "59") (name "Net-(Q4-PadG)") (class "Default")
      (node (ref "Q4") (pin "G") (pinfunction "G_G") (pintype "passive"))
      (node (ref "R5") (pin "2") (pinfunction "2_2") (pintype "passive"))
    )
    (net (code "60") (name "Net-(R1-PadP$1)") (class "Default")
      (node (ref "R1") (pin "P$1") (pinfunction "P$1_P$1") (pintype "passive"))
      (node (ref "R24") (pin "2") (pinfunction "2_2") (pintype "passive"))
    )
    (net (code "61") (name "Net-(R1-PadP$2)") (class "Default")
      (node (ref "R1") (pin "P$2") (pinfunction "P$2_P$2") (pintype "passive"))
      (node (ref "R23") (pin "2") (pinfunction "2_2") (pintype "passive"))
    )
    (net (code "62") (name "Net-(R16-Pad2)") (class "Default")
      (node (ref "R16") (pin "2") (pinfunction "2_2") (pintype "passive"))
      (node (ref "R18") (pin "1") (pinfunction "1_1") (pintype "passive"))
    )
    (net (code "63") (name "Net-(U$2-C1)") (class "Default")
      (node (ref "R6") (pin "2") (pinfunction "2_2") (pintype "passive"))
      (node (ref "U$2") (pin "2") (pinfunction "C1_2") (pintype "bidirectional"))
    )
    (net (code "64") (name "Net-(U$2-C2)") (class "Default")
      (node (ref "R7") (pin "2") (pinfunction "2_2") (pintype "passive"))
      (node (ref "U$2") (pin "3") (pinfunction "C2_3") (pintype "bidirectional"))
    )
    (net (code "65") (name "Net-(U$7-DE)") (class "Default")
      (node (ref "U$7") (pin "2") (pinfunction "RE_2") (pintype "bidirectional"))
      (node (ref "U$7") (pin "3") (pinfunction "DE_3") (pintype "bidirectional"))
    )
    (net (code "66") (name "Net-(U1-CB)") (class "Default")
      (node (ref "C15") (pin "1") (pinfunction "1_1") (pintype "passive"))
      (node (ref "U1") (pin "1") (pinfunction "CB_1") (pintype "bidirectional"))
    )
    (net (code "67") (name "Net-(U1-FB)") (class "Default")
      (node (ref "R10") (pin "2") (pinfunction "2_2") (pintype "passive"))
      (node (ref "R11") (pin "2") (pinfunction "2_2") (pintype "passive"))
      (node (ref "U1") (pin "3") (pinfunction "FB_3") (pintype "bidirectional"))
    )
    (net (code "68") (name "Net-(U1-SW)") (class "Default")
      (node (ref "C15") (pin "2") (pinfunction "2_2") (pintype "passive"))
      (node (ref "D3") (pin "C") (pinfunction "C_C") (pintype "passive"))
      (node (ref "L1") (pin "1") (pinfunction "1_1") (pintype "passive"))
      (node (ref "U1") (pin "6") (pinfunction "SW_6") (pintype "bidirectional"))
    )
    (net (code "69") (name "Net-(X1B-KL)") (class "Default")
      (node (ref "C17") (pin "+") (pinfunction "+_+") (pintype "passive"))
      (node (ref "C18") (pin "+") (pinfunction "+_+") (pintype "passive"))
      (node (ref "Q1") (pin "D") (pinfunction "D_D") (pintype "passive"))
      (node (ref "Q3") (pin "D") (pinfunction "D_D") (pintype "passive"))
      (node (ref "R18") (pin "2") (pinfunction "2_2") (pintype "passive"))
      (node (ref "SJ1") (pin "1") (pinfunction "1_1") (pintype "passive"))
      (node (ref "X1") (pin "2") (pinfunction "KL_2") (pintype "passive"))
    )
    (net (code "70") (name "unconnected-(IC1A-PA0-WKUP-Pad10)") (class "Default")
      (node (ref "IC1") (pin "10") (pinfunction "PA0-WKUP_10") (pintype "bidirectional"))
    )
    (net (code "71") (name "unconnected-(IC1A-PA3-Pad13)") (class "Default")
      (node (ref "IC1") (pin "13") (pinfunction "PA3_13") (pintype "bidirectional"))
    )
    (net (code "72") (name "unconnected-(IC1A-PA4-Pad14)") (class "Default")
      (node (ref "IC1") (pin "14") (pinfunction "PA4_14") (pintype "bidirectional"))
    )
    (net (code "73") (name "unconnected-(IC1A-PA5-Pad15)") (class "Default")
      (node (ref "IC1") (pin "15") (pinfunction "PA5_15") (pintype "bidirectional"))
    )
    (net (code "74") (name "unconnected-(IC1A-PA6-Pad16)") (class "Default")
      (node (ref "IC1") (pin "16") (pinfunction "PA6_16") (pintype "bidirectional"))
    )
    (net (code "75") (name "unconnected-(IC1A-PB1-Pad19)") (class "Default")
      (node (ref "IC1") (pin "19") (pinfunction "PB1_19") (pintype "bidirectional"))
    )
    (net (code "76") (name "unconnected-(IC1A-PB2-Pad20)") (class "Default")
      (node (ref "IC1") (pin "20") (pinfunction "PB2_20") (pintype "bidirectional"))
    )
    (net (code "77") (name "unconnected-(IC1A-PB10-Pad21)") (class "Default")
      (node (ref "IC1") (pin "21") (pinfunction "PB10_21") (pintype "bidirectional"))
    )
    (net (code "78") (name "unconnected-(IC1A-PB13-Pad26)") (class "Default")
      (node (ref "IC1") (pin "26") (pinfunction "PB13_26") (pintype "bidirectional"))
    )
    (net (code "79") (name "unconnected-(IC1A-PB14-Pad27)") (class "Default")
      (node (ref "IC1") (pin "27") (pinfunction "PB14_27") (pintype "bidirectional"))
    )
    (net (code "80") (name "unconnected-(IC1A-PC13-Pad2)") (class "Default")
      (node (ref "IC1") (pin "2") (pinfunction "PC13_2") (pintype "bidirectional"))
    )
    (net (code "81") (name "unconnected-(IC1A-PC14-Pad3)") (class "Default")
      (node (ref "IC1") (pin "3") (pinfunction "PC14_3") (pintype "bidirectional"))
    )
    (net (code "82") (name "unconnected-(IC1A-PC15-Pad4)") (class "Default")
      (node (ref "IC1") (pin "4") (pinfunction "PC15_4") (pintype "bidirectional"))
    )
    (net (code "83") (name "unconnected-(JP1-ID-Pad4)") (class "Default")
      (node (ref "JP1") (pin "4") (pinfunction "ID_4") (pintype "bidirectional"))
    )
    (net (code "84") (name "unconnected-(JP1-VCC-Pad1)") (class "Default")
      (node (ref "JP1") (pin "1") (pinfunction "VCC_1") (pintype "bidirectional"))
    )
    (net (code "85") (name "unconnected-(U$1-3A-Pad10)") (class "Default")
      (node (ref "U$1") (pin "10") (pinfunction "3A_10") (pintype "bidirectional"))
    )
    (net (code "86") (name "unconnected-(U$1-3B-Pad9)") (class "Default")
      (node (ref "U$1") (pin "9") (pinfunction "3B_9") (pintype "bidirectional"))
    )
    (net (code "87") (name "unconnected-(U$1-3Y-Pad11)") (class "Default")
      (node (ref "U$1") (pin "11") (pinfunction "3Y_11") (pintype "bidirectional"))
    )
    (net (code "88") (name "unconnected-(U$1-4A-Pad14)") (class "Default")
      (node (ref "U$1") (pin "14") (pinfunction "4A_14") (pintype "bidirectional"))
    )
    (net (code "89") (name "unconnected-(U$1-4B-Pad15)") (class "Default")
      (node (ref "U$1") (pin "15") (pinfunction "4B_15") (pintype "bidirectional"))
    )
    (net (code "90") (name "unconnected-(U$1-4Y-Pad13)") (class "Default")
      (node (ref "U$1") (pin "13") (pinfunction "4Y_13") (pintype "bidirectional"))
    )
    (net (code "91") (name "unconnected-(U$3-Pad4)") (class "Default")
      (node (ref "U$3") (pin "4") (pinfunction "4_4") (pintype "passive"))
    )
    (net (code "92") (name "unconnected-(U$3-Pad5)") (class "Default")
      (node (ref "U$3") (pin "5") (pinfunction "5_5") (pintype "passive"))
    )
  )
)
